# ADC_-_DAC.net
KiCad netlist of a schematic drawn in EAGLE
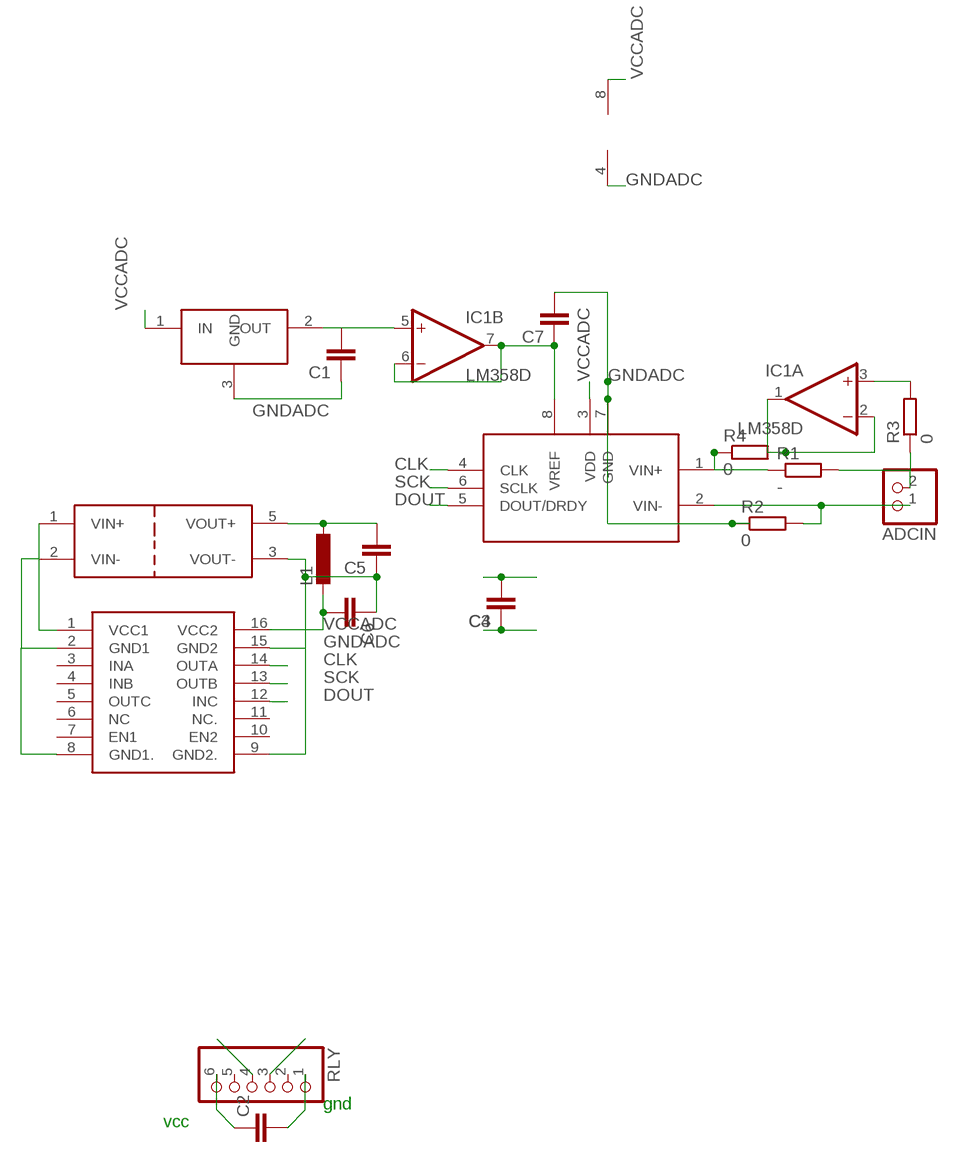
[diagram p0: schematic, sheet 1]

(export (version "E")
  (design (tool "Eeschema 10.0.6"))
  (components
    (comp (ref "ADCIN")
      (value "PINHD-1X2")
      (footprint "eagle-import:1X02")
      (libsource (lib "eagle-import") (part "PINHD-1X2"))
    )
    (comp (ref "C1")
      (value "C-EUC0805")
      (footprint "eagle-import:C0805")
      (libsource (lib "eagle-import") (part "C-EUC0805"))
    )
    (comp (ref "C2")
      (value "C-EUC0805")
      (footprint "eagle-import:C0805")
      (libsource (lib "eagle-import") (part "C-EUC0805"))
    )
    (comp (ref "C3")
      (value "C-EUC0805")
      (footprint "eagle-import:C0805")
      (libsource (lib "eagle-import") (part "C-EUC0805"))
    )
    (comp (ref "C4")
      (value "C-EUC0805")
      (footprint "eagle-import:C0805")
      (libsource (lib "eagle-import") (part "C-EUC0805"))
    )
    (comp (ref "C5")
      (value "C-EUC0805")
      (footprint "eagle-import:C0805")
      (libsource (lib "eagle-import") (part "C-EUC0805"))
    )
    (comp (ref "C6")
      (value "C-EUC0805")
      (footprint "eagle-import:C0805")
      (libsource (lib "eagle-import") (part "C-EUC0805"))
    )
    (comp (ref "C7")
      (value "C-EUC0805")
      (footprint "eagle-import:C0805")
      (libsource (lib "eagle-import") (part "C-EUC0805"))
    )
    (comp (ref "IC1")
      (value "LM358D")
      (footprint "eagle-import:SO08")
      (libsource (lib "eagle-import") (part "LM358D"))
    )
    (comp (ref "L1")
      (value "L-EUL2012C")
      (footprint "eagle-import:L2012C")
      (libsource (lib "eagle-import") (part "L-EUL2012C"))
    )
    (comp (ref "R1")
      (value "-")
      (footprint "eagle-import:M0805")
      (libsource (lib "eagle-import") (part "R-EU_M0805"))
    )
    (comp (ref "R2")
      (value "0")
      (footprint "eagle-import:M0805")
      (libsource (lib "eagle-import") (part "R-EU_M0805"))
    )
    (comp (ref "R3")
      (value "0")
      (footprint "eagle-import:M0805")
      (libsource (lib "eagle-import") (part "R-EU_M0805"))
    )
    (comp (ref "R4")
      (value "0")
      (footprint "eagle-import:M0805")
      (libsource (lib "eagle-import") (part "R-EU_M0805"))
    )
    (comp (ref "RLY")
      (value "PINHD-1X6")
      (footprint "eagle-import:1X06")
      (libsource (lib "eagle-import") (part "PINHD-1X6"))
    )
    (comp (ref "U$1")
      (value "ADS1251U")
      (footprint "eagle-import:SOIC8")
      (libsource (lib "eagle-import") (part "ADS1251U"))
    )
    (comp (ref "U$2")
      (value "REF31")
      (footprint "eagle-import:SOT23")
      (libsource (lib "eagle-import") (part "REF31"))
    )
    (comp (ref "U$3")
      (value "ISO7631")
      (footprint "eagle-import:SOIC16R")
      (libsource (lib "eagle-import") (part "ISO7631"))
    )
    (comp (ref "U$4")
      (value "DCH01")
      (footprint "eagle-import:DCH01")
      (libsource (lib "eagle-import") (part "DCH01"))
    )
  )
  (nets
    (net (code "1") (name "/CLK") (class "Default")
      (node (ref "U$1") (pin "4") (pinfunction "CLK_4") (pintype "bidirectional"))
      (node (ref "U$3") (pin "14") (pinfunction "OUTA_14") (pintype "bidirectional"))
    )
    (net (code "2") (name "/DOUT") (class "Default")
      (node (ref "U$1") (pin "5") (pinfunction "DOUT/DRDY_5") (pintype "bidirectional"))
      (node (ref "U$3") (pin "12") (pinfunction "INC_12") (pintype "bidirectional"))
    )
    (net (code "3") (name "/GNDADC") (class "Default")
      (node (ref "C1") (pin "1") (pinfunction "1_1") (pintype "passive"))
      (node (ref "C3") (pin "1") (pinfunction "1_1") (pintype "passive"))
      (node (ref "C4") (pin "1") (pinfunction "1_1") (pintype "passive"))
      (node (ref "C5") (pin "1") (pinfunction "1_1") (pintype "passive"))
      (node (ref "C6") (pin "1") (pinfunction "1_1") (pintype "passive"))
      (node (ref "C7") (pin "2") (pinfunction "2_2") (pintype "passive"))
      (node (ref "IC1") (pin "4") (pinfunction "V-_4") (pintype "power_in"))
      (node (ref "R2") (pin "1") (pinfunction "1_1") (pintype "passive"))
      (node (ref "U$1") (pin "7") (pinfunction "GND_7") (pintype "bidirectional"))
      (node (ref "U$2") (pin "3") (pinfunction "GND_3") (pintype "bidirectional"))
      (node (ref "U$3") (pin "15") (pinfunction "GND2_15") (pintype "bidirectional"))
      (node (ref "U$3") (pin "9") (pinfunction "GND2._9") (pintype "bidirectional"))
      (node (ref "U$4") (pin "3") (pinfunction "VOUT-_3") (pintype "bidirectional"))
    )
    (net (code "4") (name "/SCK") (class "Default")
      (node (ref "U$1") (pin "6") (pinfunction "SCLK_6") (pintype "bidirectional"))
      (node (ref "U$3") (pin "13") (pinfunction "OUTB_13") (pintype "bidirectional"))
    )
    (net (code "5") (name "/VCCADC") (class "Default")
      (node (ref "C3") (pin "2") (pinfunction "2_2") (pintype "passive"))
      (node (ref "C4") (pin "2") (pinfunction "2_2") (pintype "passive"))
      (node (ref "C6") (pin "2") (pinfunction "2_2") (pintype "passive"))
      (node (ref "IC1") (pin "8") (pinfunction "V+_8") (pintype "power_in"))
      (node (ref "L1") (pin "2") (pinfunction "2_2") (pintype "passive"))
      (node (ref "U$1") (pin "3") (pinfunction "VDD_3") (pintype "bidirectional"))
      (node (ref "U$2") (pin "1") (pinfunction "IN_1") (pintype "bidirectional"))
      (node (ref "U$3") (pin "16") (pinfunction "VCC2_16") (pintype "bidirectional"))
    )
    (net (code "6") (name "Net-(ADCIN-Pad2)") (class "Default")
      (node (ref "ADCIN") (pin "2") (pinfunction "2_2") (pintype "passive"))
      (node (ref "R1") (pin "2") (pinfunction "2_2") (pintype "passive"))
      (node (ref "R3") (pin "1") (pinfunction "1_1") (pintype "passive"))
    )
    (net (code "7") (name "Net-(C2-Pad1)") (class "Default")
      (node (ref "C2") (pin "1") (pinfunction "1_1") (pintype "passive"))
      (node (ref "RLY") (pin "6") (pinfunction "6_6") (pintype "passive"))
    )
    (net (code "8") (name "Net-(C2-Pad2)") (class "Default")
      (node (ref "C2") (pin "2") (pinfunction "2_2") (pintype "passive"))
      (node (ref "RLY") (pin "1") (pinfunction "1_1") (pintype "passive"))
    )
    (net (code "9") (name "Net-(IC1A-+IN)") (class "Default")
      (node (ref "IC1") (pin "3") (pinfunction "+IN_3") (pintype "input"))
      (node (ref "R3") (pin "2") (pinfunction "2_2") (pintype "passive"))
    )
    (net (code "10") (name "Net-(IC1A--IN)") (class "Default")
      (node (ref "IC1") (pin "1") (pinfunction "OUT_1") (pintype "output"))
      (node (ref "IC1") (pin "2") (pinfunction "-IN_2") (pintype "input"))
      (node (ref "R4") (pin "2") (pinfunction "2_2") (pintype "passive"))
    )
    (net (code "11") (name "Net-(IC1B-+IN)") (class "Default")
      (node (ref "C1") (pin "2") (pinfunction "2_2") (pintype "passive"))
      (node (ref "IC1") (pin "5") (pinfunction "+IN_5") (pintype "input"))
      (node (ref "U$2") (pin "2") (pinfunction "OUT_2") (pintype "bidirectional"))
    )
    (net (code "12") (name "Net-(IC1B--IN)") (class "Default")
      (node (ref "C7") (pin "1") (pinfunction "1_1") (pintype "passive"))
      (node (ref "IC1") (pin "6") (pinfunction "-IN_6") (pintype "input"))
      (node (ref "IC1") (pin "7") (pinfunction "OUT_7") (pintype "output"))
      (node (ref "U$1") (pin "8") (pinfunction "VREF_8") (pintype "bidirectional"))
    )
    (net (code "13") (name "Net-(U$1-VIN+)") (class "Default")
      (node (ref "R1") (pin "1") (pinfunction "1_1") (pintype "passive"))
      (node (ref "R4") (pin "1") (pinfunction "1_1") (pintype "passive"))
      (node (ref "U$1") (pin "1") (pinfunction "VIN+_1") (pintype "bidirectional"))
    )
    (net (code "14") (name "Net-(U$1-VIN-)") (class "Default")
      (node (ref "ADCIN") (pin "1") (pinfunction "1_1") (pintype "passive"))
      (node (ref "R2") (pin "2") (pinfunction "2_2") (pintype "passive"))
      (node (ref "U$1") (pin "2") (pinfunction "VIN-_2") (pintype "bidirectional"))
    )
    (net (code "15") (name "Net-(U$3-GND1)") (class "Default")
      (node (ref "U$3") (pin "2") (pinfunction "GND1_2") (pintype "bidirectional"))
      (node (ref "U$3") (pin "8") (pinfunction "GND1._8") (pintype "bidirectional"))
      (node (ref "U$4") (pin "2") (pinfunction "VIN-_2") (pintype "bidirectional"))
    )
    (net (code "16") (name "Net-(U$3-VCC1)") (class "Default")
      (node (ref "U$3") (pin "1") (pinfunction "VCC1_1") (pintype "bidirectional"))
      (node (ref "U$4") (pin "1") (pinfunction "VIN+_1") (pintype "bidirectional"))
    )
    (net (code "17") (name "Net-(U$4-VOUT+)") (class "Default")
      (node (ref "C5") (pin "2") (pinfunction "2_2") (pintype "passive"))
      (node (ref "L1") (pin "1") (pinfunction "1_1") (pintype "passive"))
      (node (ref "U$4") (pin "5") (pinfunction "VOUT+_5") (pintype "bidirectional"))
    )
    (net (code "18") (name "unconnected-(RLY-Pad2)") (class "Default")
      (node (ref "RLY") (pin "2") (pinfunction "2_2") (pintype "passive"))
    )
    (net (code "19") (name "unconnected-(RLY-Pad3)") (class "Default")
      (node (ref "RLY") (pin "3") (pinfunction "3_3") (pintype "passive"))
    )
    (net (code "20") (name "unconnected-(RLY-Pad4)") (class "Default")
      (node (ref "RLY") (pin "4") (pinfunction "4_4") (pintype "passive"))
    )
    (net (code "21") (name "unconnected-(RLY-Pad5)") (class "Default")
      (node (ref "RLY") (pin "5") (pinfunction "5_5") (pintype "passive"))
    )
    (net (code "22") (name "unconnected-(U$3-EN1-Pad7)") (class "Default")
      (node (ref "U$3") (pin "7") (pinfunction "EN1_7") (pintype "bidirectional"))
    )
    (net (code "23") (name "unconnected-(U$3-EN2-Pad10)") (class "Default")
      (node (ref "U$3") (pin "10") (pinfunction "EN2_10") (pintype "bidirectional"))
    )
    (net (code "24") (name "unconnected-(U$3-INA-Pad3)") (class "Default")
      (node (ref "U$3") (pin "3") (pinfunction "INA_3") (pintype "bidirectional"))
    )
    (net (code "25") (name "unconnected-(U$3-INB-Pad4)") (class "Default")
      (node (ref "U$3") (pin "4") (pinfunction "INB_4") (pintype "bidirectional"))
    )
    (net (code "26") (name "unconnected-(U$3-NC-Pad6)") (class "Default")
      (node (ref "U$3") (pin "6") (pinfunction "NC_6") (pintype "bidirectional"))
    )
    (net (code "27") (name "unconnected-(U$3-NC.-Pad11)") (class "Default")
      (node (ref "U$3") (pin "11") (pinfunction "NC._11") (pintype "bidirectional"))
    )
    (net (code "28") (name "unconnected-(U$3-OUTC-Pad5)") (class "Default")
      (node (ref "U$3") (pin "5") (pinfunction "OUTC_5") (pintype "bidirectional"))
    )
  )
)
